# RackEth_rev_2.net
KiCad netlist of a schematic drawn in EasyEDA Pro
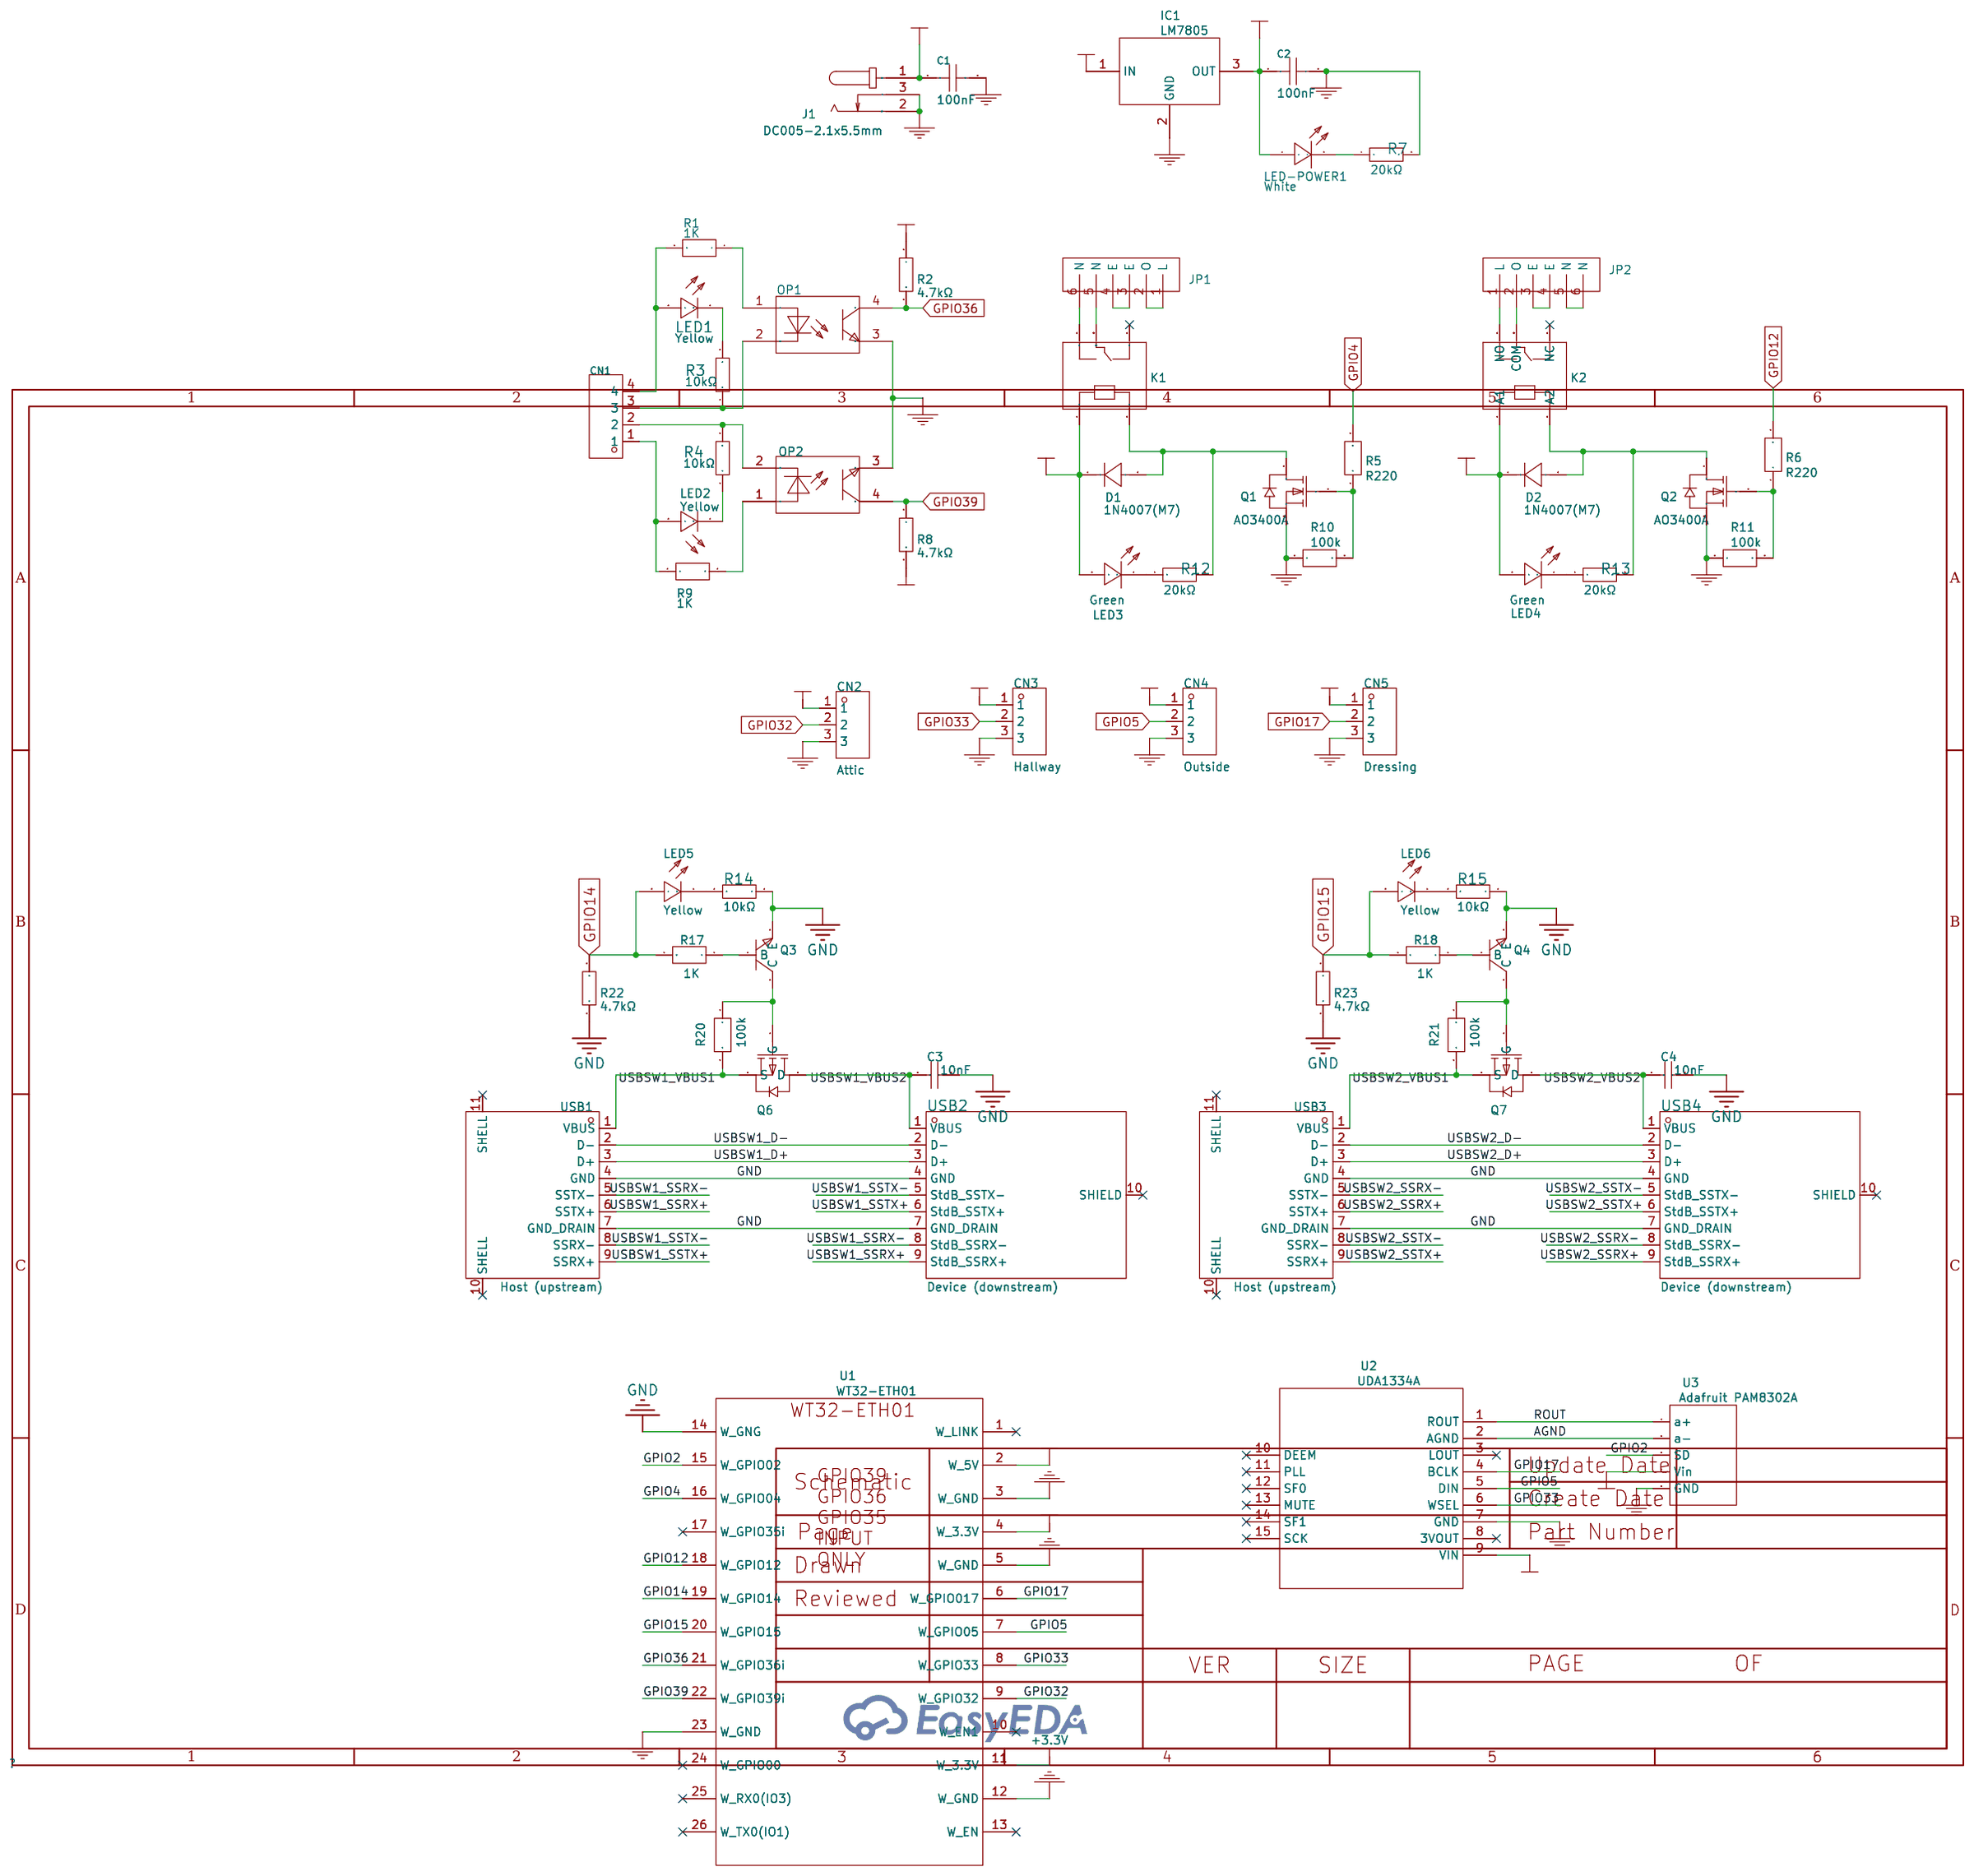
[diagram p0: schematic sheet]

(export (version "E")
  (design (tool "Eeschema 10.0.6"))
  (components
    (comp (ref "C1")
      (value "100nF")
      (footprint "easyedapro:C0603")
      (fields
        (field (name "Manufacturer Part") "CC0603KRX7R9BB104")
        (field (name "Manufacturer") "YAGEO(国巨)")
      )
      (libsource (lib "easyedapro") (part "CC0603KRX7R9BB104"))
    )
    (comp (ref "C2")
      (value "100nF")
      (footprint "easyedapro:C0603")
      (fields
        (field (name "Manufacturer Part") "CC0603KRX7R9BB104")
        (field (name "Manufacturer") "YAGEO(国巨)")
      )
      (libsource (lib "easyedapro") (part "CC0603KRX7R9BB104"))
    )
    (comp (ref "C3")
      (value "10nF")
      (footprint "easyedapro:C0402")
      (fields
        (field (name "Manufacturer Part") "CL05B103KB5NNNC")
        (field (name "Manufacturer") "SAMSUNG(三星)")
      )
      (libsource (lib "easyedapro") (part "CL05B103KB5NNNC"))
    )
    (comp (ref "C4")
      (value "10nF")
      (footprint "easyedapro:C0402")
      (fields
        (field (name "Manufacturer Part") "CL05B103KB5NNNC")
        (field (name "Manufacturer") "SAMSUNG(三星)")
      )
      (libsource (lib "easyedapro") (part "CL05B103KB5NNNC"))
    )
    (comp (ref "CN1")
      (value "WJ127-5.0-4P")
      (footprint "easyedapro:CONN-TH_4P-P5.00_WJ127-5.0-4P")
      (fields (field (name "Manufacturer") "KANGNEX(康奈克斯电气)"))
      (libsource (lib "easyedapro") (part "WJ127-5.0-4P"))
    )
    (comp (ref "CN2")
      (value "Attic")
      (footprint "easyedapro:CONN-TH_3P-P2.50_HCTL_XH-3A-L")
      (fields (field (name "Manufacturer Part") "XH2.54-3A"))
      (libsource (lib "easyedapro") (part "XH2.54-3A"))
    )
    (comp (ref "CN3")
      (value "Hallway")
      (footprint "easyedapro:CONN-TH_3P-P2.50_HCTL_XH-3A-L")
      (fields (field (name "Manufacturer Part") "XH2.54-3A"))
      (libsource (lib "easyedapro") (part "XH2.54-3A"))
    )
    (comp (ref "CN4")
      (value "Outside")
      (footprint "easyedapro:CONN-TH_3P-P2.50_HCTL_XH-3A-L")
      (fields (field (name "Manufacturer Part") "XH2.54-3A"))
      (libsource (lib "easyedapro") (part "XH2.54-3A"))
    )
    (comp (ref "CN5")
      (value "Dressing")
      (footprint "easyedapro:CONN-TH_3P-P2.50_HCTL_XH-3A-L")
      (fields (field (name "Manufacturer Part") "XH2.54-3A"))
      (libsource (lib "easyedapro") (part "XH2.54-3A"))
    )
    (comp (ref "D1")
      (value "1N4007(M7)")
      (footprint "easyedapro:SMA_L4.3-W2.7-LS5.1-RD")
      (fields (field (name "Manufacturer") "UMW(友台半导体)"))
      (libsource (lib "easyedapro") (part "1N4007(M7)"))
    )
    (comp (ref "D2")
      (value "1N4007(M7)")
      (footprint "easyedapro:SMA_L4.3-W2.7-LS5.1-RD")
      (fields (field (name "Manufacturer") "UMW(友台半导体)"))
      (libsource (lib "easyedapro") (part "1N4007(M7)"))
    )
    (comp (ref "IC1")
      (value "LM7805")
      (footprint "easyedapro:LM7805")
      (libsource (lib "easyedapro") (part "LM7805"))
    )
    (comp (ref "J1")
      (value "DC005-2.1x5.5mm")
      (footprint "easyedapro:DC-IN-TH_POWER-JACK")
      (fields (field (name "Manufacturer Part") "POWER-JACK") (field (name "Manufacturer") "索峰"))
      (libsource (lib "easyedapro") (part "DC005-2.1x5.5mm"))
    )
    (comp (ref "JP1") (value "JP1") (libsource (lib "easyedapro") (part "Terminal?")))
    (comp (ref "JP2") (value "JP2") (libsource (lib "easyedapro") (part "Terminal?")))
    (comp (ref "K1")
      (value "Relay1")
      (footprint "easyedapro:SRD-05VDC-SL-C_RELAY_SRD-05VDC-SL-C")
      (libsource (lib "easyedapro") (part "Relay1"))
    )
    (comp (ref "K2")
      (value "Relay2")
      (footprint "easyedapro:SRD-05VDC-SL-C_RELAY_SRD-05VDC-SL-C")
      (libsource (lib "easyedapro") (part "Relay2"))
    )
    (comp (ref "LED-POWER1")
      (value "White")
      (footprint "easyedapro:LED0603-R-RD_WHITE")
      (fields (field (name "Manufacturer Part") "KT-0603W") (field (name "Manufacturer") "KENTO"))
      (libsource (lib "easyedapro") (part "0603White light_C2290"))
    )
    (comp (ref "LED1")
      (value "Yellow")
      (footprint "easyedapro:LED0603-RD-YELLOW")
      (fields
        (field (name "Manufacturer Part") "19-213/Y2C-CQ2R2L/3T(CY)")
        (field (name "Manufacturer") "EVERLIGHT(亿光)")
      )
      (libsource (lib "easyedapro") (part "19-213/Y2C-CQ2R2L/3T(CY)"))
    )
    (comp (ref "LED2")
      (value "Yellow")
      (footprint "easyedapro:LED0603-RD-YELLOW")
      (fields
        (field (name "Manufacturer Part") "19-213/Y2C-CQ2R2L/3T(CY)")
        (field (name "Manufacturer") "EVERLIGHT(亿光)")
      )
      (libsource (lib "easyedapro") (part "19-213/Y2C-CQ2R2L/3T(CY)"))
    )
    (comp (ref "LED3")
      (value "Green")
      (footprint "easyedapro:LED0805-RD_GREEN")
      (fields (field (name "Manufacturer Part") "0805G (Green)") (field (name "Manufacturer") "KENTO"))
      (libsource (lib "easyedapro") (part "0805G (Green)"))
    )
    (comp (ref "LED4")
      (value "Green")
      (footprint "easyedapro:LED0805-RD_GREEN")
      (fields (field (name "Manufacturer Part") "0805G (Green)") (field (name "Manufacturer") "KENTO"))
      (libsource (lib "easyedapro") (part "0805G (Green)"))
    )
    (comp (ref "LED5")
      (value "Yellow")
      (footprint "easyedapro:LED0603-RD-YELLOW")
      (fields
        (field (name "Manufacturer Part") "19-213/Y2C-CQ2R2L/3T(CY)")
        (field (name "Manufacturer") "EVERLIGHT(亿光)")
      )
      (libsource (lib "easyedapro") (part "19-213/Y2C-CQ2R2L/3T(CY)"))
    )
    (comp (ref "LED6")
      (value "Yellow")
      (footprint "easyedapro:LED0603-RD-YELLOW")
      (fields
        (field (name "Manufacturer Part") "19-213/Y2C-CQ2R2L/3T(CY)")
        (field (name "Manufacturer") "EVERLIGHT(亿光)")
      )
      (libsource (lib "easyedapro") (part "19-213/Y2C-CQ2R2L/3T(CY)"))
    )
    (comp (ref "OP1")
      (value "EL817S1(C)(TU)-F")
      (footprint "easyedapro:OPTO-SMD-4_L4.6-W6.5-P2.54-LS10.3-TL")
      (fields (field (name "Manufacturer") "EVERLIGHT(亿光)"))
      (libsource (lib "easyedapro") (part "EL817S1(C)(TU)-F"))
    )
    (comp (ref "OP2")
      (value "EL817S1(C)(TU)-F")
      (footprint "easyedapro:OPTO-SMD-4_L4.6-W6.5-P2.54-LS10.3-TL")
      (fields (field (name "Manufacturer") "EVERLIGHT(亿光)"))
      (libsource (lib "easyedapro") (part "EL817S1(C)(TU)-F"))
    )
    (comp (ref "Q1")
      (value "AO3400A")
      (footprint "easyedapro:SOT-23-3_L2.9-W1.6-P1.90-LS2.8-BR")
      (fields (field (name "Manufacturer") "AOS"))
      (libsource (lib "easyedapro") (part "AO3400A"))
    )
    (comp (ref "Q2")
      (value "AO3400A")
      (footprint "easyedapro:SOT-23-3_L2.9-W1.6-P1.90-LS2.8-BR")
      (fields (field (name "Manufacturer") "AOS"))
      (libsource (lib "easyedapro") (part "AO3400A"))
    )
    (comp (ref "Q3")
      (value "MMBT3904(RANGE:100-300)")
      (footprint "easyedapro:SOT-23-3_L2.9-W1.3-P1.90-LS2.4-BR")
      (fields (field (name "Manufacturer") "CJ(江苏长电/长晶)"))
      (libsource (lib "easyedapro") (part "MMBT3904"))
    )
    (comp (ref "Q4")
      (value "MMBT3904(RANGE:100-300)")
      (footprint "easyedapro:SOT-23-3_L2.9-W1.3-P1.90-LS2.4-BR")
      (fields (field (name "Manufacturer") "CJ(江苏长电/长晶)"))
      (libsource (lib "easyedapro") (part "MMBT3904"))
    )
    (comp (ref "Q6")
      (value "AO3401A")
      (footprint "easyedapro:SOT-23_L2.9-W1.3-P1.90-LS2.4-BR")
      (fields (field (name "Manufacturer") "AOS"))
      (libsource (lib "easyedapro") (part "AO3401A"))
    )
    (comp (ref "Q7")
      (value "AO3401A")
      (footprint "easyedapro:SOT-23_L2.9-W1.3-P1.90-LS2.4-BR")
      (fields (field (name "Manufacturer") "AOS"))
      (libsource (lib "easyedapro") (part "AO3401A"))
    )
    (comp (ref "R1")
      (value "1K")
      (footprint "easyedapro:R0603")
      (fields
        (field (name "Manufacturer Part") "0603WAF1001T5E")
        (field (name "Manufacturer") "UNI-ROYAL(厚声)")
      )
      (libsource (lib "easyedapro") (part "1K"))
    )
    (comp (ref "R2")
      (value "4.7kΩ")
      (footprint "easyedapro:R0603")
      (fields
        (field (name "Manufacturer Part") "0603WAF4701T5E")
        (field (name "Manufacturer") "UNI-ROYAL(厚声)")
      )
      (libsource (lib "easyedapro") (part "0603WAF4701T5E"))
    )
    (comp (ref "R3")
      (value "10kΩ")
      (footprint "easyedapro:R0603")
      (fields
        (field (name "Manufacturer Part") "0603WAF1002T5E")
        (field (name "Manufacturer") "UNI-ROYAL(厚声)")
      )
      (libsource (lib "easyedapro") (part "0603WAF1002T5E"))
    )
    (comp (ref "R4")
      (value "10kΩ")
      (footprint "easyedapro:R0603")
      (fields
        (field (name "Manufacturer Part") "0603WAF1002T5E")
        (field (name "Manufacturer") "UNI-ROYAL(厚声)")
      )
      (libsource (lib "easyedapro") (part "0603WAF1002T5E"))
    )
    (comp (ref "R5")
      (value "R220")
      (footprint "easyedapro:R0603")
      (fields
        (field (name "Manufacturer Part") "0603WAF2200T5E")
        (field (name "Manufacturer") "UNI-ROYAL(厚声)")
      )
      (libsource (lib "easyedapro") (part "R220"))
    )
    (comp (ref "R6")
      (value "R220")
      (footprint "easyedapro:R0603")
      (fields
        (field (name "Manufacturer Part") "0603WAF2200T5E")
        (field (name "Manufacturer") "UNI-ROYAL(厚声)")
      )
      (libsource (lib "easyedapro") (part "R220"))
    )
    (comp (ref "R7")
      (value "20kΩ")
      (footprint "easyedapro:R0603")
      (fields
        (field (name "Manufacturer Part") "0603WAF2002T5E")
        (field (name "Manufacturer") "UNI-ROYAL(厚声)")
      )
      (libsource (lib "easyedapro") (part "0603WAF2002T5E"))
    )
    (comp (ref "R8")
      (value "4.7kΩ")
      (footprint "easyedapro:R0603")
      (fields
        (field (name "Manufacturer Part") "0603WAF4701T5E")
        (field (name "Manufacturer") "UNI-ROYAL(厚声)")
      )
      (libsource (lib "easyedapro") (part "0603WAF4701T5E"))
    )
    (comp (ref "R9")
      (value "1K")
      (footprint "easyedapro:R0603")
      (fields
        (field (name "Manufacturer Part") "0603WAF1001T5E")
        (field (name "Manufacturer") "UNI-ROYAL(厚声)")
      )
      (libsource (lib "easyedapro") (part "1K"))
    )
    (comp (ref "R10")
      (value "100k")
      (footprint "easyedapro:R0603")
      (fields
        (field (name "Manufacturer Part") "0603WAF1003T5E")
        (field (name "Manufacturer") "UNI-ROYAL(厚声)")
      )
      (libsource (lib "easyedapro") (part "100k"))
    )
    (comp (ref "R11")
      (value "100k")
      (footprint "easyedapro:R0603")
      (fields
        (field (name "Manufacturer Part") "0603WAF1003T5E")
        (field (name "Manufacturer") "UNI-ROYAL(厚声)")
      )
      (libsource (lib "easyedapro") (part "100k"))
    )
    (comp (ref "R12")
      (value "20kΩ")
      (footprint "easyedapro:R0603")
      (fields
        (field (name "Manufacturer Part") "0603WAF2002T5E")
        (field (name "Manufacturer") "UNI-ROYAL(厚声)")
      )
      (libsource (lib "easyedapro") (part "0603WAF2002T5E"))
    )
    (comp (ref "R13")
      (value "20kΩ")
      (footprint "easyedapro:R0603")
      (fields
        (field (name "Manufacturer Part") "0603WAF2002T5E")
        (field (name "Manufacturer") "UNI-ROYAL(厚声)")
      )
      (libsource (lib "easyedapro") (part "0603WAF2002T5E"))
    )
    (comp (ref "R14")
      (value "10kΩ")
      (footprint "easyedapro:R0603")
      (fields
        (field (name "Manufacturer Part") "0603WAF1002T5E")
        (field (name "Manufacturer") "UNI-ROYAL(厚声)")
      )
      (libsource (lib "easyedapro") (part "0603WAF1002T5E"))
    )
    (comp (ref "R15")
      (value "10kΩ")
      (footprint "easyedapro:R0603")
      (fields
        (field (name "Manufacturer Part") "0603WAF1002T5E")
        (field (name "Manufacturer") "UNI-ROYAL(厚声)")
      )
      (libsource (lib "easyedapro") (part "0603WAF1002T5E"))
    )
    (comp (ref "R17")
      (value "1K")
      (footprint "easyedapro:R0603")
      (fields
        (field (name "Manufacturer Part") "0603WAF1001T5E")
        (field (name "Manufacturer") "UNI-ROYAL(厚声)")
      )
      (libsource (lib "easyedapro") (part "1K"))
    )
    (comp (ref "R18")
      (value "1K")
      (footprint "easyedapro:R0603")
      (fields
        (field (name "Manufacturer Part") "0603WAF1001T5E")
        (field (name "Manufacturer") "UNI-ROYAL(厚声)")
      )
      (libsource (lib "easyedapro") (part "1K"))
    )
    (comp (ref "R20")
      (value "100k")
      (footprint "easyedapro:R0603")
      (fields
        (field (name "Manufacturer Part") "0603WAF1003T5E")
        (field (name "Manufacturer") "UNI-ROYAL(厚声)")
      )
      (libsource (lib "easyedapro") (part "100k"))
    )
    (comp (ref "R21")
      (value "100k")
      (footprint "easyedapro:R0603")
      (fields
        (field (name "Manufacturer Part") "0603WAF1003T5E")
        (field (name "Manufacturer") "UNI-ROYAL(厚声)")
      )
      (libsource (lib "easyedapro") (part "100k"))
    )
    (comp (ref "R22")
      (value "4.7kΩ")
      (footprint "easyedapro:R0603")
      (fields
        (field (name "Manufacturer Part") "0603WAF4701T5E")
        (field (name "Manufacturer") "UNI-ROYAL(厚声)")
      )
      (libsource (lib "easyedapro") (part "0603WAF4701T5E"))
    )
    (comp (ref "R23")
      (value "4.7kΩ")
      (footprint "easyedapro:R0603")
      (fields
        (field (name "Manufacturer Part") "0603WAF4701T5E")
        (field (name "Manufacturer") "UNI-ROYAL(厚声)")
      )
      (libsource (lib "easyedapro") (part "0603WAF4701T5E"))
    )
    (comp (ref "U1")
      (value "WT32-ETH01")
      (footprint "easyedapro:WT32-ETH01-M")
      (fields (field (name "Manufacturer") "Wireless-Tag"))
      (libsource (lib "easyedapro") (part "WT32-ETH01"))
    )
    (comp (ref "U2")
      (value "UDA1334A")
      (footprint "easyedapro:UDA1334A_MODULE")
      (libsource (lib "easyedapro") (part "UDA1334A module"))
    )
    (comp (ref "U3")
      (value "Adafruit PAM8302A")
      (footprint "easyedapro:ADAFRUIT PAM8302A")
      (libsource (lib "easyedapro") (part "Adafruit PAM8302A"))
    )
    (comp (ref "USB1")
      (value "Host (upstream)")
      (footprint "easyedapro:USB3.0-TH_U235-09XN-2XC2-002")
      (fields
        (field (name "Manufacturer Part") "U235-091N-2UC2-002")
        (field (name "Manufacturer") "XKB Connection(中国星坤)")
      )
      (libsource (lib "easyedapro") (part "U235-091N-2UC2-002"))
    )
    (comp (ref "USB2")
      (value "Device (downstream)")
      (footprint "easyedapro:USB3.0-A-SMD_916-862A205EY10200")
      (fields (field (name "Manufacturer Part") "916-862A205EY10200") (field (name "Manufacturer") "精拓金"))
      (libsource (lib "easyedapro") (part "916-862A205EY10200"))
    )
    (comp (ref "USB3")
      (value "Host (upstream)")
      (footprint "easyedapro:USB3.0-TH_U235-09XN-2XC2-002")
      (fields
        (field (name "Manufacturer Part") "U235-091N-2UC2-002")
        (field (name "Manufacturer") "XKB Connection(中国星坤)")
      )
      (libsource (lib "easyedapro") (part "U235-091N-2UC2-002"))
    )
    (comp (ref "USB4")
      (value "Device (downstream)")
      (footprint "easyedapro:USB3.0-A-SMD_916-862A205EY10200")
      (fields (field (name "Manufacturer Part") "916-862A205EY10200") (field (name "Manufacturer") "精拓金"))
      (libsource (lib "easyedapro") (part "916-862A205EY10200"))
    )
  )
  (nets
    (net (code "1") (name "+3.3V") (class "Default")
      (node (ref "CN2") (pin "1") (pinfunction "1_1") (pintype "unspecified"))
      (node (ref "CN3") (pin "1") (pinfunction "1_1") (pintype "unspecified"))
      (node (ref "CN4") (pin "1") (pinfunction "1_1") (pintype "unspecified"))
      (node (ref "CN5") (pin "1") (pinfunction "1_1") (pintype "unspecified"))
      (node (ref "U1") (pin "11") (pinfunction "W_3.3V_11") (pintype "unspecified"))
    )
    (net (code "2") (name "+3.3V_2") (class "Default")
      (node (ref "R2") (pin "1") (pinfunction "1_1") (pintype "input"))
      (node (ref "R8") (pin "2") (pinfunction "2_2") (pintype "input"))
      (node (ref "U1") (pin "4") (pinfunction "W_3.3V_4") (pintype "unspecified"))
    )
    (net (code "3") (name "+5V") (class "Default")
      (node (ref "C2") (pin "1") (pinfunction "1_1") (pintype "input"))
      (node (ref "D1") (pin "1") (pinfunction "K_1") (pintype "unspecified"))
      (node (ref "D2") (pin "1") (pinfunction "K_1") (pintype "unspecified"))
      (node (ref "IC1") (pin "3") (pinfunction "OUT_3") (pintype "unspecified"))
      (node (ref "K1") (pin "A1") (pinfunction "A1_A1") (pintype "unspecified"))
      (node (ref "K2") (pin "A1") (pinfunction "A1_A1") (pintype "unspecified"))
      (node (ref "LED-POWER1") (pin "1") (pinfunction "A_1") (pintype "unspecified"))
      (node (ref "LED3") (pin "2") (pinfunction "A_2") (pintype "unspecified"))
      (node (ref "LED4") (pin "2") (pinfunction "A_2") (pintype "unspecified"))
      (node (ref "U1") (pin "2") (pinfunction "W_5V_2") (pintype "unspecified"))
      (node (ref "U2") (pin "9") (pinfunction "VIN_9") (pintype "unspecified"))
      (node (ref "U3") (pin "4") (pinfunction "Vin_4") (pintype "input"))
    )
    (net (code "4") (name "/AGND") (class "Default")
      (node (ref "U2") (pin "2") (pinfunction "AGND_2") (pintype "unspecified"))
      (node (ref "U3") (pin "2") (pinfunction "a-_2") (pintype "input"))
    )
    (net (code "5") (name "/GPIO2") (class "Default")
      (node (ref "U1") (pin "15") (pinfunction "W_GPIO02_15") (pintype "unspecified"))
      (node (ref "U3") (pin "3") (pinfunction "SD_3") (pintype "input"))
    )
    (net (code "6") (name "/ROUT") (class "Default")
      (node (ref "U2") (pin "1") (pinfunction "ROUT_1") (pintype "unspecified"))
      (node (ref "U3") (pin "1") (pinfunction "a+_1") (pintype "input"))
    )
    (net (code "7") (name "/USBSW1_D+") (class "Default")
      (node (ref "USB1") (pin "3") (pinfunction "D+_3") (pintype "unspecified"))
      (node (ref "USB2") (pin "3") (pinfunction "D+_3") (pintype "input"))
    )
    (net (code "8") (name "/USBSW1_D-") (class "Default")
      (node (ref "USB1") (pin "2") (pinfunction "D-_2") (pintype "unspecified"))
      (node (ref "USB2") (pin "2") (pinfunction "D-_2") (pintype "input"))
    )
    (net (code "9") (name "/USBSW1_SSRX+") (class "Default")
      (node (ref "USB1") (pin "6") (pinfunction "SSTX+_6") (pintype "unspecified"))
      (node (ref "USB2") (pin "9") (pinfunction "StdB_SSRX+_9") (pintype "input"))
    )
    (net (code "10") (name "/USBSW1_SSRX-") (class "Default")
      (node (ref "USB1") (pin "5") (pinfunction "SSTX-_5") (pintype "unspecified"))
      (node (ref "USB2") (pin "8") (pinfunction "StdB_SSRX-_8") (pintype "input"))
    )
    (net (code "11") (name "/USBSW1_SSTX+") (class "Default")
      (node (ref "USB1") (pin "9") (pinfunction "SSRX+_9") (pintype "unspecified"))
      (node (ref "USB2") (pin "6") (pinfunction "StdB_SSTX+_6") (pintype "input"))
    )
    (net (code "12") (name "/USBSW1_SSTX-") (class "Default")
      (node (ref "USB1") (pin "8") (pinfunction "SSRX-_8") (pintype "unspecified"))
      (node (ref "USB2") (pin "5") (pinfunction "StdB_SSTX-_5") (pintype "input"))
    )
    (net (code "13") (name "/USBSW1_VBUS1") (class "Default")
      (node (ref "Q6") (pin "2") (pinfunction "S_2") (pintype "unspecified"))
      (node (ref "R20") (pin "2") (pinfunction "2_2") (pintype "unspecified"))
      (node (ref "USB1") (pin "1") (pinfunction "VBUS_1") (pintype "unspecified"))
    )
    (net (code "14") (name "/USBSW1_VBUS2") (class "Default")
      (node (ref "C3") (pin "2") (pinfunction "2_2") (pintype "input"))
      (node (ref "Q6") (pin "3") (pinfunction "D_3") (pintype "unspecified"))
      (node (ref "USB2") (pin "1") (pinfunction "VBUS_1") (pintype "input"))
    )
    (net (code "15") (name "/USBSW2_D+") (class "Default")
      (node (ref "USB3") (pin "3") (pinfunction "D+_3") (pintype "unspecified"))
      (node (ref "USB4") (pin "3") (pinfunction "D+_3") (pintype "input"))
    )
    (net (code "16") (name "/USBSW2_D-") (class "Default")
      (node (ref "USB3") (pin "2") (pinfunction "D-_2") (pintype "unspecified"))
      (node (ref "USB4") (pin "2") (pinfunction "D-_2") (pintype "input"))
    )
    (net (code "17") (name "/USBSW2_SSRX+") (class "Default")
      (node (ref "USB3") (pin "6") (pinfunction "SSTX+_6") (pintype "unspecified"))
      (node (ref "USB4") (pin "9") (pinfunction "StdB_SSRX+_9") (pintype "input"))
    )
    (net (code "18") (name "/USBSW2_SSRX-") (class "Default")
      (node (ref "USB3") (pin "5") (pinfunction "SSTX-_5") (pintype "unspecified"))
      (node (ref "USB4") (pin "8") (pinfunction "StdB_SSRX-_8") (pintype "input"))
    )
    (net (code "19") (name "/USBSW2_SSTX+") (class "Default")
      (node (ref "USB3") (pin "9") (pinfunction "SSRX+_9") (pintype "unspecified"))
      (node (ref "USB4") (pin "6") (pinfunction "StdB_SSTX+_6") (pintype "input"))
    )
    (net (code "20") (name "/USBSW2_SSTX-") (class "Default")
      (node (ref "USB3") (pin "8") (pinfunction "SSRX-_8") (pintype "unspecified"))
      (node (ref "USB4") (pin "5") (pinfunction "StdB_SSTX-_5") (pintype "input"))
    )
    (net (code "21") (name "/USBSW2_VBUS1") (class "Default")
      (node (ref "Q7") (pin "2") (pinfunction "S_2") (pintype "unspecified"))
      (node (ref "R21") (pin "2") (pinfunction "2_2") (pintype "unspecified"))
      (node (ref "USB3") (pin "1") (pinfunction "VBUS_1") (pintype "unspecified"))
    )
    (net (code "22") (name "/USBSW2_VBUS2") (class "Default")
      (node (ref "C4") (pin "2") (pinfunction "2_2") (pintype "input"))
      (node (ref "Q7") (pin "3") (pinfunction "D_3") (pintype "unspecified"))
      (node (ref "USB4") (pin "1") (pinfunction "VBUS_1") (pintype "input"))
    )
    (net (code "23") (name "GND") (class "Default")
      (node (ref "C1") (pin "2") (pinfunction "2_2") (pintype "input"))
      (node (ref "C2") (pin "2") (pinfunction "2_2") (pintype "input"))
      (node (ref "C3") (pin "1") (pinfunction "1_1") (pintype "input"))
      (node (ref "C4") (pin "1") (pinfunction "1_1") (pintype "input"))
      (node (ref "CN2") (pin "3") (pinfunction "3_3") (pintype "unspecified"))
      (node (ref "CN3") (pin "3") (pinfunction "3_3") (pintype "unspecified"))
      (node (ref "CN4") (pin "3") (pinfunction "3_3") (pintype "unspecified"))
      (node (ref "CN5") (pin "3") (pinfunction "3_3") (pintype "unspecified"))
      (node (ref "IC1") (pin "2") (pinfunction "GND_2") (pintype "unspecified"))
      (node (ref "J1") (pin "2") (pinfunction "GND_2") (pintype "unspecified"))
      (node (ref "J1") (pin "3") (pinfunction "3_3") (pintype "unspecified"))
      (node (ref "OP1") (pin "3") (pinfunction "EM_3") (pintype "unspecified"))
      (node (ref "OP2") (pin "3") (pinfunction "EM_3") (pintype "unspecified"))
      (node (ref "Q1") (pin "2") (pinfunction "S_2") (pintype "unspecified"))
      (node (ref "Q2") (pin "2") (pinfunction "S_2") (pintype "unspecified"))
      (node (ref "Q3") (pin "2") (pinfunction "E_2") (pintype "unspecified"))
      (node (ref "Q4") (pin "2") (pinfunction "E_2") (pintype "unspecified"))
      (node (ref "R10") (pin "1") (pinfunction "1_1") (pintype "unspecified"))
      (node (ref "R11") (pin "1") (pinfunction "1_1") (pintype "unspecified"))
      (node (ref "R14") (pin "1") (pinfunction "1_1") (pintype "input"))
      (node (ref "R15") (pin "1") (pinfunction "1_1") (pintype "input"))
      (node (ref "R22") (pin "2") (pinfunction "2_2") (pintype "input"))
      (node (ref "R23") (pin "2") (pinfunction "2_2") (pintype "input"))
      (node (ref "R7") (pin "2") (pinfunction "2_2") (pintype "input"))
      (node (ref "U1") (pin "12") (pinfunction "W_GND_12") (pintype "unspecified"))
      (node (ref "U1") (pin "14") (pinfunction "W_GNG_14") (pintype "unspecified"))
      (node (ref "U1") (pin "23") (pinfunction "W_GND_23") (pintype "unspecified"))
      (node (ref "U1") (pin "3") (pinfunction "W_GND_3") (pintype "unspecified"))
      (node (ref "U1") (pin "5") (pinfunction "W_GND_5") (pintype "unspecified"))
      (node (ref "U2") (pin "7") (pinfunction "GND_7") (pintype "unspecified"))
      (node (ref "U3") (pin "5") (pinfunction "GND_5") (pintype "input"))
      (node (ref "USB1") (pin "4") (pinfunction "GND_4") (pintype "unspecified"))
      (node (ref "USB1") (pin "7") (pinfunction "GND_DRAIN_7") (pintype "unspecified"))
      (node (ref "USB2") (pin "4") (pinfunction "GND_4") (pintype "input"))
      (node (ref "USB2") (pin "7") (pinfunction "GND_DRAIN_7") (pintype "input"))
      (node (ref "USB3") (pin "4") (pinfunction "GND_4") (pintype "unspecified"))
      (node (ref "USB3") (pin "7") (pinfunction "GND_DRAIN_7") (pintype "unspecified"))
      (node (ref "USB4") (pin "4") (pinfunction "GND_4") (pintype "input"))
      (node (ref "USB4") (pin "7") (pinfunction "GND_DRAIN_7") (pintype "input"))
    )
    (net (code "24") (name "GPIO4") (class "Default")
      (node (ref "R5") (pin "2") (pinfunction "2_2") (pintype "unspecified"))
      (node (ref "U1") (pin "16") (pinfunction "W_GPIO04_16") (pintype "unspecified"))
    )
    (net (code "25") (name "GPIO5") (class "Default")
      (node (ref "CN4") (pin "2") (pinfunction "2_2") (pintype "unspecified"))
      (node (ref "U1") (pin "7") (pinfunction "W_GPIO05_7") (pintype "unspecified"))
      (node (ref "U2") (pin "5") (pinfunction "DIN_5") (pintype "unspecified"))
    )
    (net (code "26") (name "GPIO12") (class "Default")
      (node (ref "R6") (pin "2") (pinfunction "2_2") (pintype "unspecified"))
      (node (ref "U1") (pin "18") (pinfunction "W_GPIO12_18") (pintype "unspecified"))
    )
    (net (code "27") (name "GPIO14") (class "Default")
      (node (ref "LED5") (pin "2") (pinfunction "A_2") (pintype "input"))
      (node (ref "R17") (pin "2") (pinfunction "2_2") (pintype "unspecified"))
      (node (ref "R22") (pin "1") (pinfunction "1_1") (pintype "input"))
      (node (ref "U1") (pin "19") (pinfunction "W_GPIO14_19") (pintype "unspecified"))
    )
    (net (code "28") (name "GPIO15") (class "Default")
      (node (ref "LED6") (pin "2") (pinfunction "A_2") (pintype "input"))
      (node (ref "R18") (pin "2") (pinfunction "2_2") (pintype "unspecified"))
      (node (ref "R23") (pin "1") (pinfunction "1_1") (pintype "input"))
      (node (ref "U1") (pin "20") (pinfunction "W_GPIO15_20") (pintype "unspecified"))
    )
    (net (code "29") (name "GPIO17") (class "Default")
      (node (ref "CN5") (pin "2") (pinfunction "2_2") (pintype "unspecified"))
      (node (ref "U1") (pin "6") (pinfunction "W_GPIO017_6") (pintype "unspecified"))
      (node (ref "U2") (pin "4") (pinfunction "BCLK_4") (pintype "unspecified"))
    )
    (net (code "30") (name "GPIO32") (class "Default")
      (node (ref "CN2") (pin "2") (pinfunction "2_2") (pintype "unspecified"))
      (node (ref "U1") (pin "9") (pinfunction "W_GPIO32_9") (pintype "unspecified"))
    )
    (net (code "31") (name "GPIO33") (class "Default")
      (node (ref "CN3") (pin "2") (pinfunction "2_2") (pintype "unspecified"))
      (node (ref "U1") (pin "8") (pinfunction "W_GPIO33_8") (pintype "unspecified"))
      (node (ref "U2") (pin "6") (pinfunction "WSEL_6") (pintype "unspecified"))
    )
    (net (code "32") (name "GPIO36") (class "Default")
      (node (ref "OP1") (pin "4") (pinfunction "COL_4") (pintype "unspecified"))
      (node (ref "R2") (pin "2") (pinfunction "2_2") (pintype "input"))
      (node (ref "U1") (pin "21") (pinfunction "W_GPIO36i_21") (pintype "unspecified"))
    )
    (net (code "33") (name "GPIO39") (class "Default")
      (node (ref "OP2") (pin "4") (pinfunction "COL_4") (pintype "unspecified"))
      (node (ref "R8") (pin "1") (pinfunction "1_1") (pintype "input"))
      (node (ref "U1") (pin "22") (pinfunction "W_GPIO39i_22") (pintype "unspecified"))
    )
    (net (code "34") (name "Net-(D1-A)") (class "Default")
      (node (ref "D1") (pin "2") (pinfunction "A_2") (pintype "unspecified"))
      (node (ref "K1") (pin "A2") (pinfunction "A2_A2") (pintype "unspecified"))
      (node (ref "Q1") (pin "3") (pinfunction "D_3") (pintype "unspecified"))
      (node (ref "R12") (pin "2") (pinfunction "2_2") (pintype "input"))
    )
    (net (code "35") (name "Net-(D2-A)") (class "Default")
      (node (ref "D2") (pin "2") (pinfunction "A_2") (pintype "unspecified"))
      (node (ref "K2") (pin "A2") (pinfunction "A2_A2") (pintype "unspecified"))
      (node (ref "Q2") (pin "3") (pinfunction "D_3") (pintype "unspecified"))
      (node (ref "R13") (pin "2") (pinfunction "2_2") (pintype "input"))
    )
    (net (code "36") (name "Net-(JP1-E-Pad3)") (class "Default")
      (node (ref "JP1") (pin "3") (pinfunction "E_3") (pintype "unspecified"))
      (node (ref "JP1") (pin "4") (pinfunction "E_4") (pintype "unspecified"))
    )
    (net (code "37") (name "Net-(JP1-L)") (class "Default")
      (node (ref "JP1") (pin "1") (pinfunction "L_1") (pintype "unspecified"))
      (node (ref "JP1") (pin "2") (pinfunction "O_2") (pintype "unspecified"))
    )
    (net (code "38") (name "Net-(JP1-N-Pad5)") (class "Default")
      (node (ref "JP1") (pin "5") (pinfunction "N_5") (pintype "unspecified"))
      (node (ref "K1") (pin "COM") (pinfunction "COM_COM") (pintype "unspecified"))
    )
    (net (code "39") (name "Net-(JP1-N-Pad6)") (class "Default")
      (node (ref "JP1") (pin "6") (pinfunction "N_6") (pintype "unspecified"))
      (node (ref "K1") (pin "NO") (pinfunction "NO_NO") (pintype "unspecified"))
    )
    (net (code "40") (name "Net-(JP2-E-Pad3)") (class "Default")
      (node (ref "JP2") (pin "3") (pinfunction "E_3") (pintype "unspecified"))
      (node (ref "JP2") (pin "4") (pinfunction "E_4") (pintype "unspecified"))
    )
    (net (code "41") (name "Net-(JP2-L)") (class "Default")
      (node (ref "JP2") (pin "1") (pinfunction "L_1") (pintype "unspecified"))
      (node (ref "K2") (pin "NO") (pinfunction "NO_NO") (pintype "unspecified"))
    )
    (net (code "42") (name "Net-(JP2-N-Pad5)") (class "Default")
      (node (ref "JP2") (pin "5") (pinfunction "N_5") (pintype "unspecified"))
      (node (ref "JP2") (pin "6") (pinfunction "N_6") (pintype "unspecified"))
    )
    (net (code "43") (name "Net-(JP2-O)") (class "Default")
      (node (ref "JP2") (pin "2") (pinfunction "O_2") (pintype "unspecified"))
      (node (ref "K2") (pin "COM") (pinfunction "COM_COM") (pintype "unspecified"))
    )
    (net (code "44") (name "Net-(LED-POWER1-K)") (class "Default")
      (node (ref "LED-POWER1") (pin "2") (pinfunction "K_2") (pintype "unspecified"))
      (node (ref "R7") (pin "1") (pinfunction "1_1") (pintype "input"))
    )
    (net (code "45") (name "Net-(LED1-A)") (class "Default")
      (node (ref "CN1") (pin "4") (pinfunction "4_4") (pintype "input"))
      (node (ref "LED1") (pin "2") (pinfunction "A_2") (pintype "input"))
      (node (ref "R1") (pin "2") (pinfunction "2_2") (pintype "unspecified"))
    )
    (net (code "46") (name "Net-(LED1-C)") (class "Default")
      (node (ref "LED1") (pin "1") (pinfunction "C_1") (pintype "input"))
      (node (ref "R3") (pin "2") (pinfunction "2_2") (pintype "input"))
    )
    (net (code "47") (name "Net-(LED2-A)") (class "Default")
      (node (ref "CN1") (pin "1") (pinfunction "1_1") (pintype "input"))
      (node (ref "LED2") (pin "2") (pinfunction "A_2") (pintype "input"))
      (node (ref "R9") (pin "1") (pinfunction "1_1") (pintype "unspecified"))
    )
    (net (code "48") (name "Net-(LED2-C)") (class "Default")
      (node (ref "LED2") (pin "1") (pinfunction "C_1") (pintype "input"))
      (node (ref "R4") (pin "1") (pinfunction "1_1") (pintype "input"))
    )
    (net (code "49") (name "Net-(LED3-K)") (class "Default")
      (node (ref "LED3") (pin "1") (pinfunction "K_1") (pintype "unspecified"))
      (node (ref "R12") (pin "1") (pinfunction "1_1") (pintype "input"))
    )
    (net (code "50") (name "Net-(LED4-K)") (class "Default")
      (node (ref "LED4") (pin "1") (pinfunction "K_1") (pintype "unspecified"))
      (node (ref "R13") (pin "1") (pinfunction "1_1") (pintype "input"))
    )
    (net (code "51") (name "Net-(LED5-C)") (class "Default")
      (node (ref "LED5") (pin "1") (pinfunction "C_1") (pintype "input"))
      (node (ref "R14") (pin "2") (pinfunction "2_2") (pintype "input"))
    )
    (net (code "52") (name "Net-(LED6-C)") (class "Default")
      (node (ref "LED6") (pin "1") (pinfunction "C_1") (pintype "input"))
      (node (ref "R15") (pin "2") (pinfunction "2_2") (pintype "input"))
    )
    (net (code "53") (name "Net-(OP1-AN)") (class "Default")
      (node (ref "OP1") (pin "1") (pinfunction "AN_1") (pintype "unspecified"))
      (node (ref "R1") (pin "1") (pinfunction "1_1") (pintype "unspecified"))
    )
    (net (code "54") (name "Net-(OP1-CAT)") (class "Default")
      (node (ref "CN1") (pin "3") (pinfunction "3_3") (pintype "input"))
      (node (ref "OP1") (pin "2") (pinfunction "CAT_2") (pintype "unspecified"))
      (node (ref "R3") (pin "1") (pinfunction "1_1") (pintype "input"))
    )
    (net (code "55") (name "Net-(OP2-AN)") (class "Default")
      (node (ref "OP2") (pin "1") (pinfunction "AN_1") (pintype "unspecified"))
      (node (ref "R9") (pin "2") (pinfunction "2_2") (pintype "unspecified"))
    )
    (net (code "56") (name "Net-(OP2-CAT)") (class "Default")
      (node (ref "CN1") (pin "2") (pinfunction "2_2") (pintype "input"))
      (node (ref "OP2") (pin "2") (pinfunction "CAT_2") (pintype "unspecified"))
      (node (ref "R4") (pin "2") (pinfunction "2_2") (pintype "input"))
    )
    (net (code "57") (name "Net-(Q1-G)") (class "Default")
      (node (ref "Q1") (pin "1") (pinfunction "G_1") (pintype "unspecified"))
      (node (ref "R10") (pin "2") (pinfunction "2_2") (pintype "unspecified"))
      (node (ref "R5") (pin "1") (pinfunction "1_1") (pintype "unspecified"))
    )
    (net (code "58") (name "Net-(Q2-G)") (class "Default")
      (node (ref "Q2") (pin "1") (pinfunction "G_1") (pintype "unspecified"))
      (node (ref "R11") (pin "2") (pinfunction "2_2") (pintype "unspecified"))
      (node (ref "R6") (pin "1") (pinfunction "1_1") (pintype "unspecified"))
    )
    (net (code "59") (name "Net-(Q3-B)") (class "Default")
      (node (ref "Q3") (pin "1") (pinfunction "B_1") (pintype "unspecified"))
      (node (ref "R17") (pin "1") (pinfunction "1_1") (pintype "unspecified"))
    )
    (net (code "60") (name "Net-(Q3-C)") (class "Default")
      (node (ref "Q3") (pin "3") (pinfunction "C_3") (pintype "unspecified"))
      (node (ref "Q6") (pin "1") (pinfunction "G_1") (pintype "unspecified"))
      (node (ref "R20") (pin "1") (pinfunction "1_1") (pintype "unspecified"))
    )
    (net (code "61") (name "Net-(Q4-B)") (class "Default")
      (node (ref "Q4") (pin "1") (pinfunction "B_1") (pintype "unspecified"))
      (node (ref "R18") (pin "1") (pinfunction "1_1") (pintype "unspecified"))
    )
    (net (code "62") (name "Net-(Q4-C)") (class "Default")
      (node (ref "Q4") (pin "3") (pinfunction "C_3") (pintype "unspecified"))
      (node (ref "Q7") (pin "1") (pinfunction "G_1") (pintype "unspecified"))
      (node (ref "R21") (pin "1") (pinfunction "1_1") (pintype "unspecified"))
    )
    (net (code "63") (name "VCC") (class "Default")
      (node (ref "C1") (pin "1") (pinfunction "1_1") (pintype "input"))
      (node (ref "IC1") (pin "1") (pinfunction "IN_1") (pintype "unspecified"))
      (node (ref "J1") (pin "1") (pinfunction "VCC_1") (pintype "unspecified"))
    )
    (net (code "64") (name "unconnected-(K1-PadNC)") (class "Default")
      (node (ref "K1") (pin "NC") (pinfunction "NC_NC") (pintype "unspecified+no_connect"))
    )
    (net (code "65") (name "unconnected-(K2-PadNC)") (class "Default")
      (node (ref "K2") (pin "NC") (pinfunction "NC_NC") (pintype "unspecified+no_connect"))
    )
    (net (code "66") (name "unconnected-(U1-W_EN-Pad13)") (class "Default")
      (node (ref "U1") (pin "13") (pinfunction "W_EN_13") (pintype "unspecified+no_connect"))
    )
    (net (code "67") (name "unconnected-(U1-W_EN1-Pad10)") (class "Default")
      (node (ref "U1") (pin "10") (pinfunction "W_EN1_10") (pintype "unspecified+no_connect"))
    )
    (net (code "68") (name "unconnected-(U1-W_GPIO00-Pad24)") (class "Default")
      (node (ref "U1") (pin "24") (pinfunction "W_GPIO00_24") (pintype "unspecified+no_connect"))
    )
    (net (code "69") (name "unconnected-(U1-W_GPIO35i-Pad17)") (class "Default")
      (node (ref "U1") (pin "17") (pinfunction "W_GPIO35i_17") (pintype "unspecified+no_connect"))
    )
    (net (code "70") (name "unconnected-(U1-W_LINK-Pad1)") (class "Default")
      (node (ref "U1") (pin "1") (pinfunction "W_LINK_1") (pintype "unspecified+no_connect"))
    )
    (net (code "71") (name "unconnected-(U1-W_RX0(IO3)-Pad25)") (class "Default")
      (node (ref "U1") (pin "25") (pinfunction "W_RX0(IO3)_25") (pintype "unspecified+no_connect"))
    )
    (net (code "72") (name "unconnected-(U1-W_TX0(IO1)-Pad26)") (class "Default")
      (node (ref "U1") (pin "26") (pinfunction "W_TX0(IO1)_26") (pintype "unspecified+no_connect"))
    )
    (net (code "73") (name "unconnected-(U2-3VOUT-Pad8)") (class "Default")
      (node (ref "U2") (pin "8") (pinfunction "3VOUT_8") (pintype "unspecified+no_connect"))
    )
    (net (code "74") (name "unconnected-(U2-DEEM-Pad10)") (class "Default")
      (node (ref "U2") (pin "10") (pinfunction "DEEM_10") (pintype "unspecified+no_connect"))
    )
    (net (code "75") (name "unconnected-(U2-LOUT-Pad3)") (class "Default")
      (node (ref "U2") (pin "3") (pinfunction "LOUT_3") (pintype "unspecified+no_connect"))
    )
    (net (code "76") (name "unconnected-(U2-MUTE-Pad13)") (class "Default")
      (node (ref "U2") (pin "13") (pinfunction "MUTE_13") (pintype "unspecified+no_connect"))
    )
    (net (code "77") (name "unconnected-(U2-PLL-Pad11)") (class "Default")
      (node (ref "U2") (pin "11") (pinfunction "PLL_11") (pintype "unspecified+no_connect"))
    )
    (net (code "78") (name "unconnected-(U2-SCK-Pad15)") (class "Default")
      (node (ref "U2") (pin "15") (pinfunction "SCK_15") (pintype "unspecified+no_connect"))
    )
    (net (code "79") (name "unconnected-(U2-SF0-Pad12)") (class "Default")
      (node (ref "U2") (pin "12") (pinfunction "SF0_12") (pintype "unspecified+no_connect"))
    )
    (net (code "80") (name "unconnected-(U2-SF1-Pad14)") (class "Default")
      (node (ref "U2") (pin "14") (pinfunction "SF1_14") (pintype "unspecified+no_connect"))
    )
    (net (code "81") (name "unconnected-(USB1-SHELL-Pad10)") (class "Default")
      (node (ref "USB1") (pin "10") (pinfunction "SHELL_10") (pintype "unspecified+no_connect"))
    )
    (net (code "82") (name "unconnected-(USB1-SHELL-Pad11)") (class "Default")
      (node (ref "USB1") (pin "11") (pinfunction "SHELL_11") (pintype "unspecified+no_connect"))
    )
    (net (code "83") (name "unconnected-(USB2-SHIELD-Pad10)") (class "Default")
      (node (ref "USB2") (pin "10") (pinfunction "SHIELD_10") (pintype "input+no_connect"))
    )
    (net (code "84") (name "unconnected-(USB3-SHELL-Pad10)") (class "Default")
      (node (ref "USB3") (pin "10") (pinfunction "SHELL_10") (pintype "unspecified+no_connect"))
    )
    (net (code "85") (name "unconnected-(USB3-SHELL-Pad11)") (class "Default")
      (node (ref "USB3") (pin "11") (pinfunction "SHELL_11") (pintype "unspecified+no_connect"))
    )
    (net (code "86") (name "unconnected-(USB4-SHIELD-Pad10)") (class "Default")
      (node (ref "USB4") (pin "10") (pinfunction "SHIELD_10") (pintype "input+no_connect"))
    )
  )
)
